# 03_-_Amplifier_and_ADC.net
KiCad netlist of a schematic drawn in Altium Designer
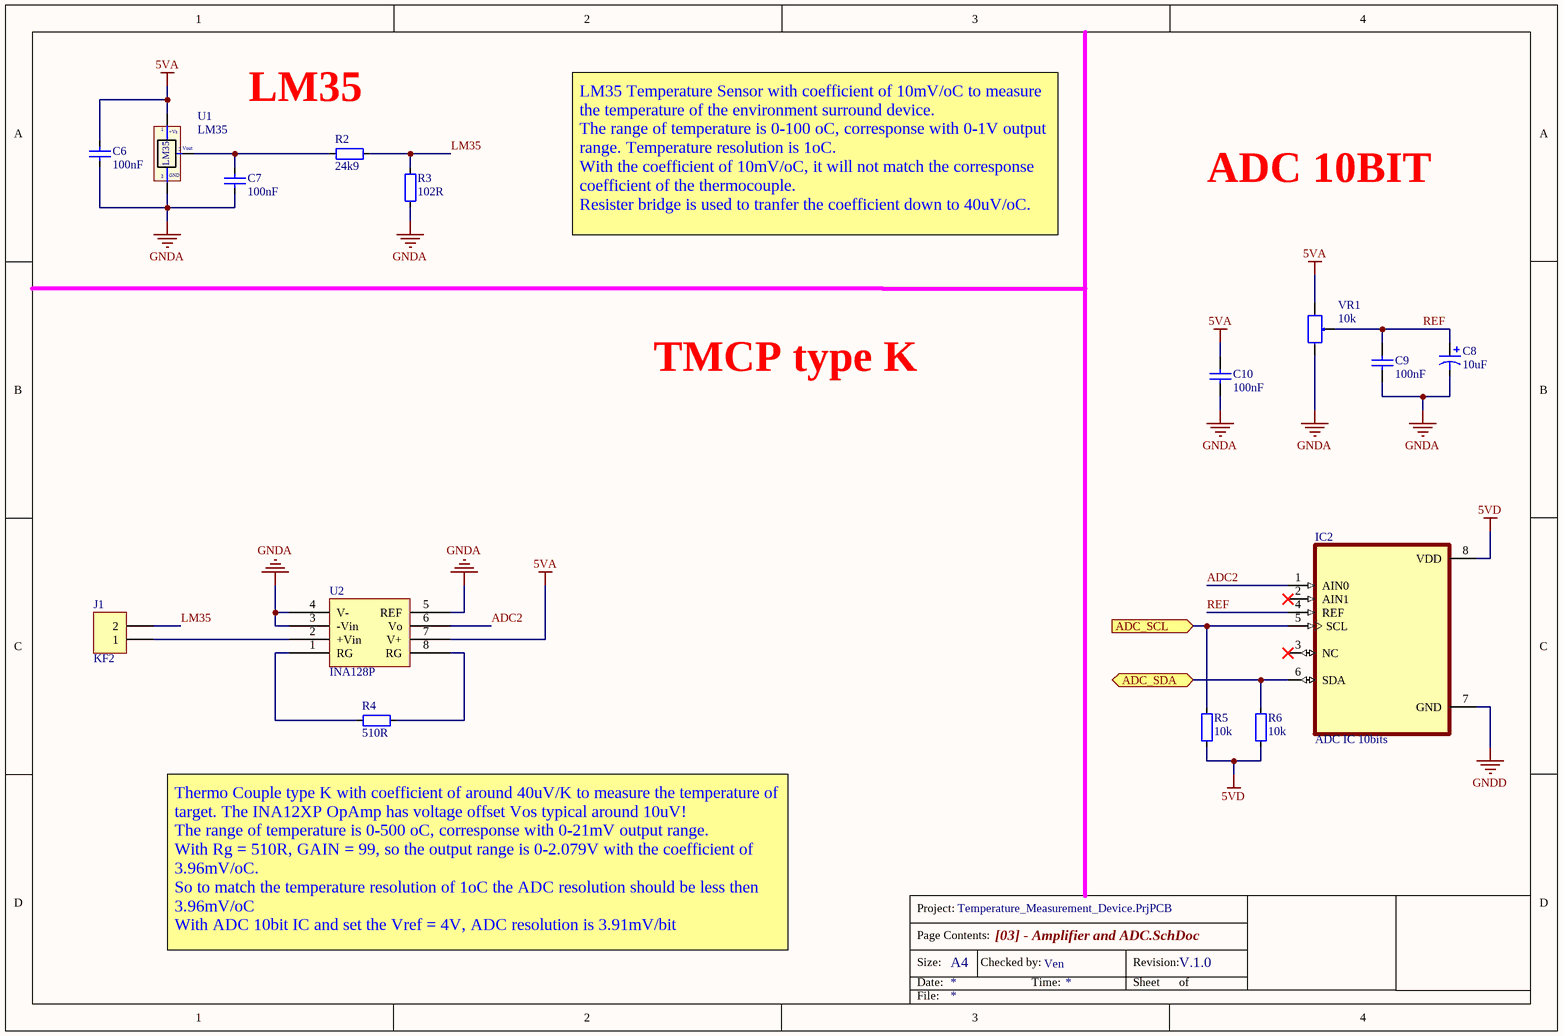
[diagram p0: [03] - Amplifier and ADC.SchDoc]

(export (version "E")
  (design (tool "Eeschema 10.0.6"))
  (components
    (comp (ref "C6")
      (value "100nF")
      (footprint "CAP_0805")
      (description "Capacitor")
      (fields (field (name "PUBLISHER") "Altium Limited"))
      (libsource (lib "My Library") (part "CapSMD"))
    )
    (comp (ref "C7")
      (value "100nF")
      (footprint "CAP_0805")
      (description "Capacitor")
      (fields (field (name "PUBLISHER") "Altium Limited"))
      (libsource (lib "My Library") (part "CapSMD"))
    )
    (comp (ref "C8")
      (value "10uF")
      (footprint "C8mm")
      (description "Polarized Capacitor (Axial)")
      (fields (field (name "PUBLISHER") "Altium Limited"))
      (libsource (lib "My Library") (part "Cap Pol"))
    )
    (comp (ref "C9")
      (value "100nF")
      (footprint "CAP_0805")
      (description "Capacitor")
      (fields (field (name "PUBLISHER") "Altium Limited"))
      (libsource (lib "") (part "CapSMD_1"))
    )
    (comp (ref "C10")
      (value "100nF")
      (footprint "CAP_0805")
      (description "Capacitor")
      (fields (field (name "PUBLISHER") "Altium Limited"))
      (libsource (lib "") (part "CapSMD_1"))
    )
    (comp (ref "IC2")
      (value "ADC IC 10bits")
      (footprint "SOP - 8 µMAX")
      (libsource (lib "My Library") (part "MAX11646"))
    )
    (comp (ref "J1")
      (value "KF2")
      (footprint "KF2-5.08T")
      (description "Couple Thermo type K")
      (fields
        (field (name "MANUFACTURER") "Würth Elektronik eiSos GmbH")
        (field (name "PARTNO") "691103110002")
        (field (name "CREATED BY") "Karrer Zheng")
      )
      (libsource (lib "My Library") (part "KF2"))
    )
    (comp (ref "R2")
      (value "24k9")
      (footprint "RES-SMD-0805")
      (description "Resistor")
      (fields
        (field (name "MANUFACTURER") "Generic Components")
        (field (name "PUBLISHER") "Altium Hobart Technology Centre")
      )
      (libsource (lib "My Library") (part "Resistor - SMD"))
    )
    (comp (ref "R3")
      (value "102R")
      (footprint "RES-SMD-0805")
      (description "Resistor")
      (fields
        (field (name "MANUFACTURER") "Generic Components")
        (field (name "PUBLISHER") "Altium Hobart Technology Centre")
      )
      (libsource (lib "My Library") (part "Resistor - SMD"))
    )
    (comp (ref "R4")
      (value "510R")
      (footprint "RES-SMD-0805")
      (description "Resistor")
      (fields
        (field (name "MANUFACTURER") "Generic Components")
        (field (name "PUBLISHER") "Altium Hobart Technology Centre")
      )
      (libsource (lib "My Library") (part "Resistor - SMD"))
    )
    (comp (ref "R5")
      (value "10k")
      (footprint "RES-SMD-0805")
      (description "Resistor")
      (fields
        (field (name "MANUFACTURER") "Generic Components")
        (field (name "PUBLISHER") "Altium Hobart Technology Centre")
      )
      (libsource (lib "My Library") (part "Resistor - SMD"))
    )
    (comp (ref "R6")
      (value "10k")
      (footprint "RES-SMD-0805")
      (description "Resistor")
      (fields
        (field (name "MANUFACTURER") "Generic Components")
        (field (name "PUBLISHER") "Altium Hobart Technology Centre")
      )
      (libsource (lib "My Library") (part "Resistor - SMD"))
    )
    (comp (ref "U1")
      (value "LM35")
      (footprint "QTO-92")
      (description "Teminal")
      (libsource (lib "My Library") (part "LM35"))
    )
    (comp (ref "U2")
      (value "INA128P")
      (footprint "SOP-8")
      (description "Instrumental Operate Amplifier")
      (libsource (lib "My Library") (part "INA129PA"))
    )
    (comp (ref "VR1")
      (value "10k")
      (footprint "VR")
      (description "Var Resistor")
      (libsource (lib "My Library") (part "VR"))
    )
  )
  (nets
    (net (code "1") (name "/ADC2") (class "Default")
      (node (ref "IC2") (pin "1") (pinfunction "AIN0_1") (pintype "input"))
      (node (ref "U2") (pin "6") (pinfunction "Vo_6") (pintype "passive"))
    )
    (net (code "2") (name "/ADC_SCL") (class "Default")
      (node (ref "IC2") (pin "5") (pinfunction "SCL_5") (pintype "input"))
      (node (ref "R5") (pin "2") (pinfunction "2_2") (pintype "passive"))
    )
    (net (code "3") (name "/ADC_SDA") (class "Default")
      (node (ref "IC2") (pin "6") (pinfunction "SDA_6") (pintype "bidirectional"))
      (node (ref "R6") (pin "2") (pinfunction "2_2") (pintype "passive"))
    )
    (net (code "4") (name "/LM35") (class "Default")
      (node (ref "J1") (pin "2") (pinfunction "2_2") (pintype "passive"))
      (node (ref "R2") (pin "1") (pinfunction "1_1") (pintype "passive"))
      (node (ref "R3") (pin "2") (pinfunction "2_2") (pintype "passive"))
    )
    (net (code "5") (name "/REF") (class "Default")
      (node (ref "C8") (pin "1") (pinfunction "1_1") (pintype "passive"))
      (node (ref "C9") (pin "2") (pinfunction "2_2") (pintype "passive"))
      (node (ref "IC2") (pin "4") (pinfunction "REF_4") (pintype "input"))
      (node (ref "VR1") (pin "2") (pinfunction "2_2") (pintype "passive"))
    )
    (net (code "6") (name "5VA") (class "Default")
      (node (ref "C10") (pin "2") (pinfunction "2_2") (pintype "passive"))
      (node (ref "C6") (pin "2") (pinfunction "2_2") (pintype "passive"))
      (node (ref "U1") (pin "1") (pinfunction "+Vs_1") (pintype "passive"))
      (node (ref "U2") (pin "7") (pinfunction "V+_7") (pintype "passive"))
      (node (ref "VR1") (pin "1") (pinfunction "1_1") (pintype "passive"))
    )
    (net (code "7") (name "5VD") (class "Default")
      (node (ref "IC2") (pin "8") (pinfunction "VDD_8") (pintype "power_in"))
      (node (ref "R5") (pin "1") (pinfunction "1_1") (pintype "passive"))
      (node (ref "R6") (pin "1") (pinfunction "1_1") (pintype "passive"))
    )
    (net (code "8") (name "GNDA") (class "Default")
      (node (ref "C10") (pin "1") (pinfunction "1_1") (pintype "passive"))
      (node (ref "C6") (pin "1") (pinfunction "1_1") (pintype "passive"))
      (node (ref "C7") (pin "1") (pinfunction "1_1") (pintype "passive"))
      (node (ref "C8") (pin "2") (pinfunction "2_2") (pintype "passive"))
      (node (ref "C9") (pin "1") (pinfunction "1_1") (pintype "passive"))
      (node (ref "R3") (pin "1") (pinfunction "1_1") (pintype "passive"))
      (node (ref "U1") (pin "3") (pinfunction "-_3") (pintype "passive"))
      (node (ref "U2") (pin "3") (pinfunction "-Vin_3") (pintype "passive"))
      (node (ref "U2") (pin "4") (pinfunction "V-_4") (pintype "passive"))
      (node (ref "U2") (pin "5") (pinfunction "REF_5") (pintype "passive"))
      (node (ref "VR1") (pin "3") (pinfunction "3_3") (pintype "passive"))
    )
    (net (code "9") (name "GNDD") (class "Default")
      (node (ref "IC2") (pin "7") (pinfunction "GND_7") (pintype "power_in"))
    )
    (net (code "10") (name "Net-(R4-Pad1)") (class "Default")
      (node (ref "R4") (pin "1") (pinfunction "1_1") (pintype "passive"))
      (node (ref "U2") (pin "1") (pinfunction "RG_1") (pintype "passive"))
    )
    (net (code "11") (name "Net-(R4-Pad2)") (class "Default")
      (node (ref "R4") (pin "2") (pinfunction "2_2") (pintype "passive"))
      (node (ref "U2") (pin "8") (pinfunction "RG_8") (pintype "passive"))
    )
    (net (code "12") (name "Net-(U1-Vout)") (class "Default")
      (node (ref "C7") (pin "2") (pinfunction "2_2") (pintype "passive"))
      (node (ref "R2") (pin "2") (pinfunction "2_2") (pintype "passive"))
      (node (ref "U1") (pin "2") (pinfunction "Vout_2") (pintype "passive"))
    )
    (net (code "13") (name "Net-(U2-+Vin)") (class "Default")
      (node (ref "J1") (pin "1") (pinfunction "1_1") (pintype "passive"))
      (node (ref "U2") (pin "2") (pinfunction "+Vin_2") (pintype "passive"))
    )
    (net (code "14") (name "unconnected-(IC2-AIN1-Pad2)") (class "Default")
      (node (ref "IC2") (pin "2") (pinfunction "AIN1_2") (pintype "input+no_connect"))
    )
    (net (code "15") (name "unconnected-(IC2-NC-Pad3)") (class "Default")
      (node (ref "IC2") (pin "3") (pinfunction "NC_3") (pintype "bidirectional+no_connect"))
    )
  )
)
